# pepitaBadge.net
KiCad netlist of a schematic drawn in EAGLE
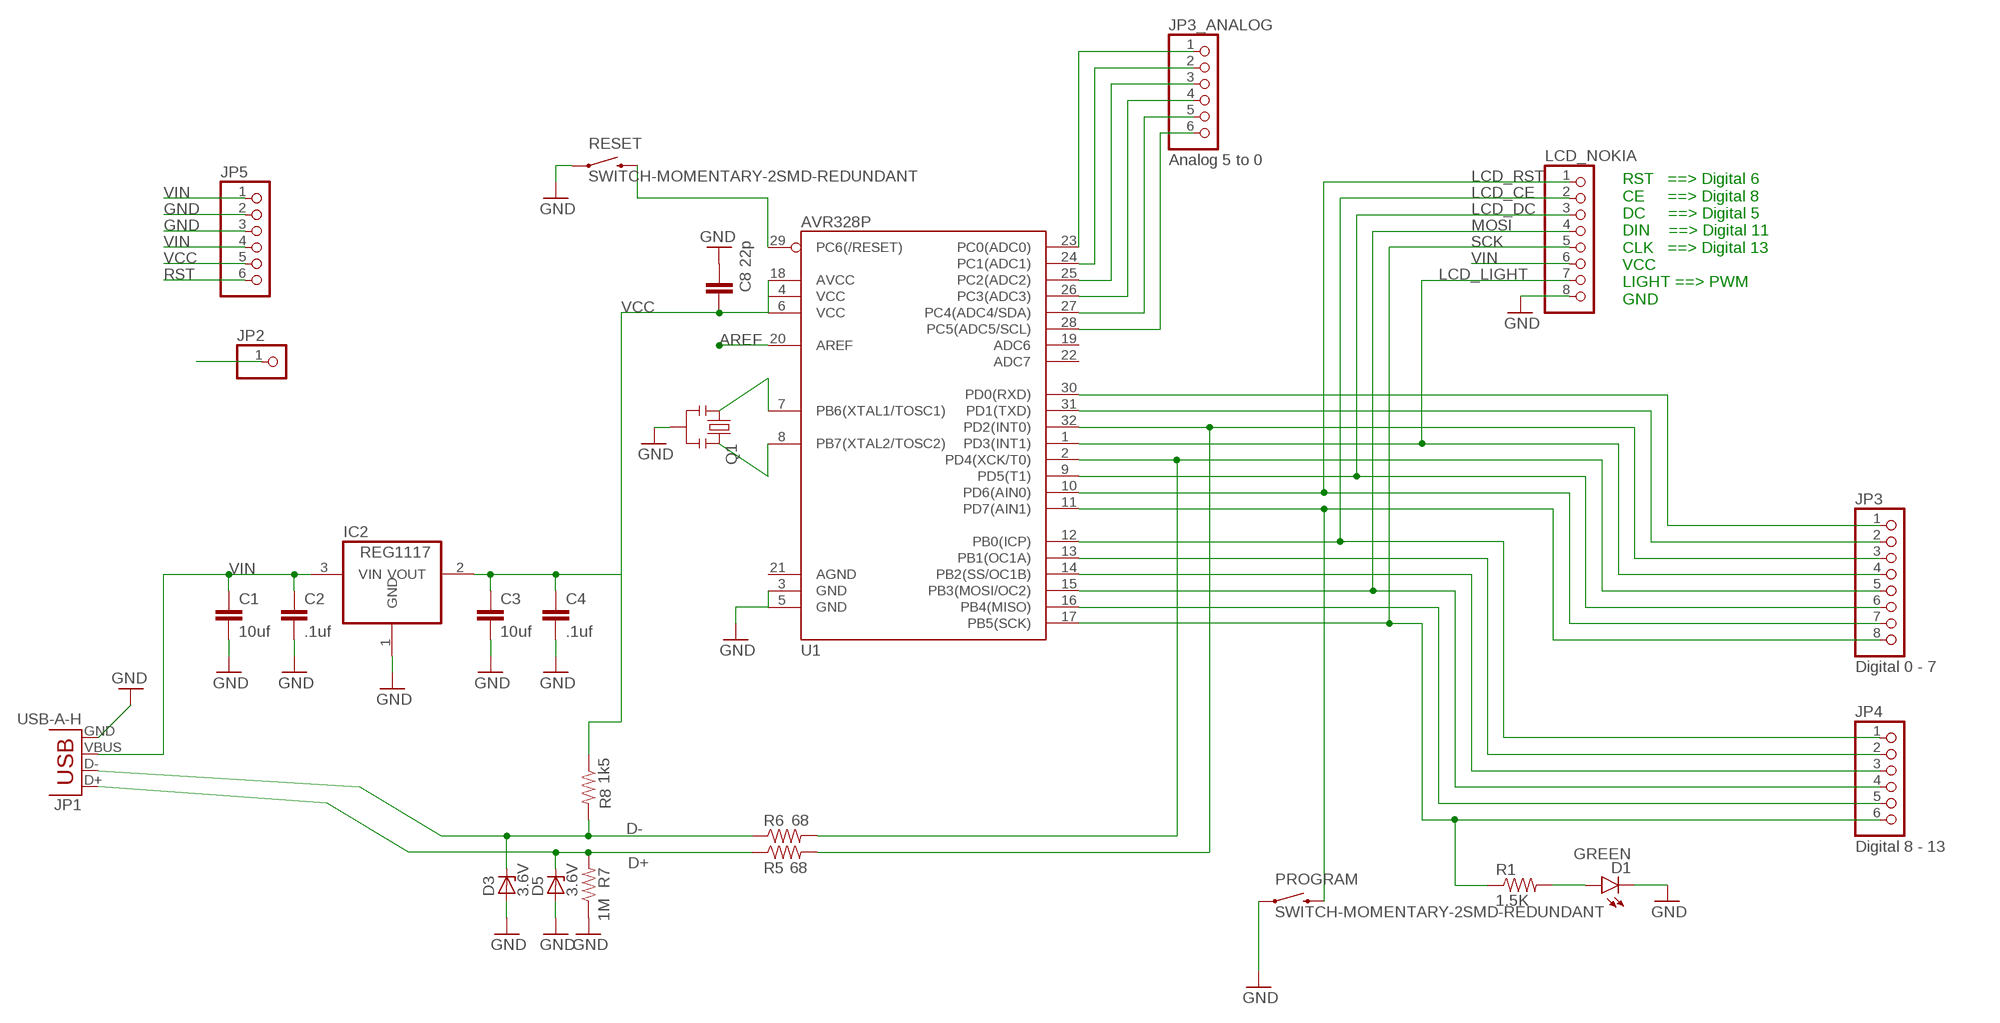
[diagram p0: schematic, sheet 1]

(export (version "E")
  (design (tool "Eeschema 10.0.6"))
  (components
    (comp (ref "C1")
      (value "10uf")
      (footprint "eagle-import:0805")
      (libsource (lib "eagle-import") (part "22UF-6.3V-20%(0805)"))
    )
    (comp (ref "C2")
      (value ".1uf")
      (footprint "eagle-import:0603-CAP")
      (libsource (lib "eagle-import") (part "CAP0603-CAP"))
    )
    (comp (ref "C3")
      (value "10uf")
      (footprint "eagle-import:0805")
      (libsource (lib "eagle-import") (part "22UF-6.3V-20%(0805)"))
    )
    (comp (ref "C4")
      (value ".1uf")
      (footprint "eagle-import:0603-CAP")
      (libsource (lib "eagle-import") (part "CAP0603-CAP"))
    )
    (comp (ref "C8")
      (value "22p")
      (footprint "eagle-import:0603-CAP")
      (libsource (lib "eagle-import") (part "CAP0603-CAP"))
    )
    (comp (ref "D1")
      (value "GREEN")
      (footprint "eagle-import:LED-0603")
      (libsource (lib "eagle-import") (part "LED-GREEN0603"))
    )
    (comp (ref "D3")
      (value "3.6V")
      (footprint "eagle-import:1206")
      (libsource (lib "eagle-import") (part "ZENER-DIODE"))
    )
    (comp (ref "D5")
      (value "3.6V")
      (footprint "eagle-import:1206")
      (libsource (lib "eagle-import") (part "ZENER-DIODE"))
    )
    (comp (ref "IC2")
      (value "REG1117")
      (footprint "eagle-import:SOT223")
      (libsource (lib "eagle-import") (part "REG1117"))
    )
    (comp (ref "JP1")
      (value "USB-A-H")
      (footprint "eagle-import:USB-A-H")
      (libsource (lib "eagle-import") (part "USB-A-H"))
    )
    (comp (ref "JP2")
      (value "PINHD-1X1")
      (footprint "eagle-import:1X01")
      (libsource (lib "eagle-import") (part "PINHD-1X1"))
    )
    (comp (ref "JP3")
      (value "Digital 0 - 7")
      (footprint "eagle-import:1X08")
      (libsource (lib "eagle-import") (part "PINHD-1X8"))
    )
    (comp (ref "JP3_ANALOG")
      (value "Analog 5 to 0")
      (footprint "eagle-import:1X06")
      (libsource (lib "eagle-import") (part "PINHD-1X6"))
    )
    (comp (ref "JP4")
      (value "Digital 8 - 13")
      (footprint "eagle-import:1X06")
      (libsource (lib "eagle-import") (part "PINHD-1X6"))
    )
    (comp (ref "JP5")
      (value "PINHD-1X6")
      (footprint "eagle-import:1X06")
      (libsource (lib "eagle-import") (part "PINHD-1X6"))
    )
    (comp (ref "LCD_NOKIA")
      (value "PINHD-1X8")
      (footprint "eagle-import:1X08")
      (libsource (lib "eagle-import") (part "PINHD-1X8"))
    )
    (comp (ref "PROGRAM")
      (value "SWITCH-MOMENTARY-2SMD-REDUNDANT")
      (footprint "eagle-import:TACTILE-SWITCH-SMD")
      (libsource (lib "eagle-import") (part "SWITCH-MOMENTARY-2SMD-REDUNDANT"))
    )
    (comp (ref "Q1")
      (value "RESONATOR16MHZ")
      (footprint "eagle-import:RESONATOR-SMD")
      (libsource (lib "eagle-import") (part "RESONATOR16MHZ"))
    )
    (comp (ref "R1")
      (value "1.5K")
      (footprint "eagle-import:0603-RES")
      (libsource (lib "eagle-import") (part "RESISTOR0603-RES"))
    )
    (comp (ref "R5")
      (value "68")
      (footprint "eagle-import:0603-RES")
      (libsource (lib "eagle-import") (part "RESISTOR0603-RES"))
    )
    (comp (ref "R6")
      (value "68")
      (footprint "eagle-import:0603-RES")
      (libsource (lib "eagle-import") (part "RESISTOR0603-RES"))
    )
    (comp (ref "R7")
      (value "1M")
      (footprint "eagle-import:0603-RES")
      (libsource (lib "eagle-import") (part "RESISTOR0603-RES"))
    )
    (comp (ref "R8")
      (value "1k5")
      (footprint "eagle-import:0603-RES")
      (libsource (lib "eagle-import") (part "RESISTOR0603-RES"))
    )
    (comp (ref "RESET")
      (value "SWITCH-MOMENTARY-2SMD-REDUNDANT")
      (footprint "eagle-import:TACTILE-SWITCH-SMD")
      (libsource (lib "eagle-import") (part "SWITCH-MOMENTARY-2SMD-REDUNDANT"))
    )
    (comp (ref "U1")
      (value "AVR328P")
      (footprint "eagle-import:TQFP32-08")
      (libsource (lib "eagle-import") (part "ATMEGA328_SMT"))
    )
  )
  (nets
    (net (code "1") (name "/AREF") (class "Default")
      (node (ref "JP2") (pin "1") (pinfunction "1_1") (pintype "passive"))
      (node (ref "U1") (pin "20") (pinfunction "AREF_20") (pintype "bidirectional"))
    )
    (net (code "2") (name "/D+") (class "Default")
      (node (ref "D5") (pin "2") (pinfunction "C_2") (pintype "passive"))
      (node (ref "JP1") (pin "D+") (pinfunction "D+_D+") (pintype "bidirectional"))
      (node (ref "R5") (pin "1") (pinfunction "1_1") (pintype "passive"))
      (node (ref "R7") (pin "2") (pinfunction "2_2") (pintype "passive"))
    )
    (net (code "3") (name "/D-") (class "Default")
      (node (ref "D3") (pin "2") (pinfunction "C_2") (pintype "passive"))
      (node (ref "JP1") (pin "D-") (pinfunction "D-_D-") (pintype "bidirectional"))
      (node (ref "R6") (pin "1") (pinfunction "1_1") (pintype "passive"))
      (node (ref "R8") (pin "2") (pinfunction "2_2") (pintype "passive"))
    )
    (net (code "4") (name "/LCD_CE") (class "Default")
      (node (ref "JP4") (pin "1") (pinfunction "1_1") (pintype "passive"))
      (node (ref "LCD_NOKIA") (pin "2") (pinfunction "2_2") (pintype "passive"))
      (node (ref "U1") (pin "12") (pinfunction "PB0(ICP)_12") (pintype "bidirectional"))
    )
    (net (code "5") (name "/LCD_DC") (class "Default")
      (node (ref "JP3") (pin "6") (pinfunction "6_6") (pintype "passive"))
      (node (ref "LCD_NOKIA") (pin "3") (pinfunction "3_3") (pintype "passive"))
      (node (ref "U1") (pin "9") (pinfunction "PD5(T1)_9") (pintype "bidirectional"))
    )
    (net (code "6") (name "/LCD_LIGHT") (class "Default")
      (node (ref "JP3") (pin "4") (pinfunction "4_4") (pintype "passive"))
      (node (ref "LCD_NOKIA") (pin "7") (pinfunction "7_7") (pintype "passive"))
      (node (ref "U1") (pin "1") (pinfunction "PD3(INT1)_1") (pintype "bidirectional"))
    )
    (net (code "7") (name "/LCD_RST") (class "Default")
      (node (ref "JP3") (pin "7") (pinfunction "7_7") (pintype "passive"))
      (node (ref "LCD_NOKIA") (pin "1") (pinfunction "1_1") (pintype "passive"))
      (node (ref "U1") (pin "10") (pinfunction "PD6(AIN0)_10") (pintype "bidirectional"))
    )
    (net (code "8") (name "/MOSI") (class "Default")
      (node (ref "JP4") (pin "4") (pinfunction "4_4") (pintype "passive"))
      (node (ref "LCD_NOKIA") (pin "4") (pinfunction "4_4") (pintype "passive"))
      (node (ref "U1") (pin "15") (pinfunction "PB3(MOSI/OC2)_15") (pintype "bidirectional"))
    )
    (net (code "9") (name "/RST") (class "Default")
      (node (ref "JP5") (pin "6") (pinfunction "6_6") (pintype "passive"))
      (node (ref "RESET") (pin "3") (pinfunction "2_3") (pintype "passive"))
      (node (ref "RESET") (pin "4") (pinfunction "2_4") (pintype "passive"))
      (node (ref "U1") (pin "29") (pinfunction "PC6(/RESET)_29") (pintype "bidirectional"))
    )
    (net (code "10") (name "/SCK") (class "Default")
      (node (ref "JP4") (pin "6") (pinfunction "6_6") (pintype "passive"))
      (node (ref "LCD_NOKIA") (pin "5") (pinfunction "5_5") (pintype "passive"))
      (node (ref "R1") (pin "1") (pinfunction "1_1") (pintype "passive"))
      (node (ref "U1") (pin "17") (pinfunction "PB5(SCK)_17") (pintype "bidirectional"))
    )
    (net (code "11") (name "/VCC") (class "Default")
      (node (ref "C3") (pin "1") (pinfunction "1_1") (pintype "passive"))
      (node (ref "C4") (pin "1") (pinfunction "1_1") (pintype "passive"))
      (node (ref "C8") (pin "1") (pinfunction "1_1") (pintype "passive"))
      (node (ref "IC2") (pin "2") (pinfunction "VOUT_2") (pintype "output"))
      (node (ref "JP5") (pin "5") (pinfunction "5_5") (pintype "passive"))
      (node (ref "R8") (pin "1") (pinfunction "1_1") (pintype "passive"))
      (node (ref "U1") (pin "18") (pinfunction "AVCC_18") (pintype "bidirectional"))
      (node (ref "U1") (pin "4") (pinfunction "VCC_4") (pintype "bidirectional"))
      (node (ref "U1") (pin "6") (pinfunction "VCC_6") (pintype "bidirectional"))
    )
    (net (code "12") (name "/VIN") (class "Default")
      (node (ref "C1") (pin "1") (pinfunction "1_1") (pintype "passive"))
      (node (ref "C2") (pin "1") (pinfunction "1_1") (pintype "passive"))
      (node (ref "IC2") (pin "3") (pinfunction "VIN_3") (pintype "input"))
      (node (ref "JP1") (pin "VBUS") (pinfunction "VBUS_VBUS") (pintype "bidirectional"))
      (node (ref "JP5") (pin "1") (pinfunction "1_1") (pintype "passive"))
      (node (ref "JP5") (pin "4") (pinfunction "4_4") (pintype "passive"))
      (node (ref "LCD_NOKIA") (pin "6") (pinfunction "6_6") (pintype "passive"))
    )
    (net (code "13") (name "GND") (class "Default")
      (node (ref "C1") (pin "2") (pinfunction "2_2") (pintype "passive"))
      (node (ref "C2") (pin "2") (pinfunction "2_2") (pintype "passive"))
      (node (ref "C3") (pin "2") (pinfunction "2_2") (pintype "passive"))
      (node (ref "C4") (pin "2") (pinfunction "2_2") (pintype "passive"))
      (node (ref "C8") (pin "2") (pinfunction "2_2") (pintype "passive"))
      (node (ref "D1") (pin "C") (pinfunction "C_C") (pintype "passive"))
      (node (ref "D3") (pin "1") (pinfunction "A_1") (pintype "passive"))
      (node (ref "D5") (pin "1") (pinfunction "A_1") (pintype "passive"))
      (node (ref "IC2") (pin "1") (pinfunction "GND_1") (pintype "power_in"))
      (node (ref "JP1") (pin "GND") (pinfunction "GND_GND") (pintype "bidirectional"))
      (node (ref "JP5") (pin "2") (pinfunction "2_2") (pintype "passive"))
      (node (ref "JP5") (pin "3") (pinfunction "3_3") (pintype "passive"))
      (node (ref "LCD_NOKIA") (pin "8") (pinfunction "8_8") (pintype "passive"))
      (node (ref "PROGRAM") (pin "1") (pinfunction "1_1") (pintype "passive"))
      (node (ref "PROGRAM") (pin "2") (pinfunction "1_2") (pintype "passive"))
      (node (ref "Q1") (pin "2") (pinfunction "2_2") (pintype "passive"))
      (node (ref "R7") (pin "1") (pinfunction "1_1") (pintype "passive"))
      (node (ref "RESET") (pin "1") (pinfunction "1_1") (pintype "passive"))
      (node (ref "RESET") (pin "2") (pinfunction "1_2") (pintype "passive"))
      (node (ref "U1") (pin "3") (pinfunction "GND_3") (pintype "bidirectional"))
      (node (ref "U1") (pin "5") (pinfunction "GND_5") (pintype "bidirectional"))
    )
    (net (code "14") (name "Net-(D1-PadA)") (class "Default")
      (node (ref "D1") (pin "A") (pinfunction "A_A") (pintype "passive"))
      (node (ref "R1") (pin "2") (pinfunction "2_2") (pintype "passive"))
    )
    (net (code "15") (name "Net-(U1-PB1(OC1A))") (class "Default")
      (node (ref "JP4") (pin "2") (pinfunction "2_2") (pintype "passive"))
      (node (ref "U1") (pin "13") (pinfunction "PB1(OC1A)_13") (pintype "bidirectional"))
    )
    (net (code "16") (name "Net-(U1-PB2(SS{slash}OC1B))") (class "Default")
      (node (ref "JP4") (pin "3") (pinfunction "3_3") (pintype "passive"))
      (node (ref "U1") (pin "14") (pinfunction "PB2(SS/OC1B)_14") (pintype "bidirectional"))
    )
    (net (code "17") (name "Net-(U1-PB4(MISO))") (class "Default")
      (node (ref "JP4") (pin "5") (pinfunction "5_5") (pintype "passive"))
      (node (ref "U1") (pin "16") (pinfunction "PB4(MISO)_16") (pintype "bidirectional"))
    )
    (net (code "18") (name "Net-(U1-PB6(XTAL1{slash}TOSC1))") (class "Default")
      (node (ref "Q1") (pin "1") (pinfunction "1_1") (pintype "passive"))
      (node (ref "U1") (pin "7") (pinfunction "PB6(XTAL1/TOSC1)_7") (pintype "bidirectional"))
    )
    (net (code "19") (name "Net-(U1-PB7(XTAL2{slash}TOSC2))") (class "Default")
      (node (ref "Q1") (pin "3") (pinfunction "3_3") (pintype "passive"))
      (node (ref "U1") (pin "8") (pinfunction "PB7(XTAL2/TOSC2)_8") (pintype "bidirectional"))
    )
    (net (code "20") (name "Net-(U1-PC0(ADC0))") (class "Default")
      (node (ref "JP3_ANALOG") (pin "1") (pinfunction "1_1") (pintype "passive"))
      (node (ref "U1") (pin "23") (pinfunction "PC0(ADC0)_23") (pintype "bidirectional"))
    )
    (net (code "21") (name "Net-(U1-PC1(ADC1))") (class "Default")
      (node (ref "JP3_ANALOG") (pin "2") (pinfunction "2_2") (pintype "passive"))
      (node (ref "U1") (pin "24") (pinfunction "PC1(ADC1)_24") (pintype "bidirectional"))
    )
    (net (code "22") (name "Net-(U1-PC2(ADC2))") (class "Default")
      (node (ref "JP3_ANALOG") (pin "3") (pinfunction "3_3") (pintype "passive"))
      (node (ref "U1") (pin "25") (pinfunction "PC2(ADC2)_25") (pintype "bidirectional"))
    )
    (net (code "23") (name "Net-(U1-PC3(ADC3))") (class "Default")
      (node (ref "JP3_ANALOG") (pin "4") (pinfunction "4_4") (pintype "passive"))
      (node (ref "U1") (pin "26") (pinfunction "PC3(ADC3)_26") (pintype "bidirectional"))
    )
    (net (code "24") (name "Net-(U1-PC4(ADC4{slash}SDA))") (class "Default")
      (node (ref "JP3_ANALOG") (pin "5") (pinfunction "5_5") (pintype "passive"))
      (node (ref "U1") (pin "27") (pinfunction "PC4(ADC4/SDA)_27") (pintype "bidirectional"))
    )
    (net (code "25") (name "Net-(U1-PC5(ADC5{slash}SCL))") (class "Default")
      (node (ref "JP3_ANALOG") (pin "6") (pinfunction "6_6") (pintype "passive"))
      (node (ref "U1") (pin "28") (pinfunction "PC5(ADC5/SCL)_28") (pintype "bidirectional"))
    )
    (net (code "26") (name "Net-(U1-PD0(RXD))") (class "Default")
      (node (ref "JP3") (pin "1") (pinfunction "1_1") (pintype "passive"))
      (node (ref "U1") (pin "30") (pinfunction "PD0(RXD)_30") (pintype "bidirectional"))
    )
    (net (code "27") (name "Net-(U1-PD1(TXD))") (class "Default")
      (node (ref "JP3") (pin "2") (pinfunction "2_2") (pintype "passive"))
      (node (ref "U1") (pin "31") (pinfunction "PD1(TXD)_31") (pintype "bidirectional"))
    )
    (net (code "28") (name "Net-(U1-PD2(INT0))") (class "Default")
      (node (ref "JP3") (pin "3") (pinfunction "3_3") (pintype "passive"))
      (node (ref "R5") (pin "2") (pinfunction "2_2") (pintype "passive"))
      (node (ref "U1") (pin "32") (pinfunction "PD2(INT0)_32") (pintype "bidirectional"))
    )
    (net (code "29") (name "Net-(U1-PD4(XCK{slash}T0))") (class "Default")
      (node (ref "JP3") (pin "5") (pinfunction "5_5") (pintype "passive"))
      (node (ref "R6") (pin "2") (pinfunction "2_2") (pintype "passive"))
      (node (ref "U1") (pin "2") (pinfunction "PD4(XCK/T0)_2") (pintype "bidirectional"))
    )
    (net (code "30") (name "Net-(U1-PD7(AIN1))") (class "Default")
      (node (ref "JP3") (pin "8") (pinfunction "8_8") (pintype "passive"))
      (node (ref "PROGRAM") (pin "3") (pinfunction "2_3") (pintype "passive"))
      (node (ref "PROGRAM") (pin "4") (pinfunction "2_4") (pintype "passive"))
      (node (ref "U1") (pin "11") (pinfunction "PD7(AIN1)_11") (pintype "bidirectional"))
    )
    (net (code "31") (name "unconnected-(U1-ADC6-Pad19)") (class "Default")
      (node (ref "U1") (pin "19") (pinfunction "ADC6_19") (pintype "bidirectional"))
    )
    (net (code "32") (name "unconnected-(U1-ADC7-Pad22)") (class "Default")
      (node (ref "U1") (pin "22") (pinfunction "ADC7_22") (pintype "bidirectional"))
    )
    (net (code "33") (name "unconnected-(U1-AGND-Pad21)") (class "Default")
      (node (ref "U1") (pin "21") (pinfunction "AGND_21") (pintype "bidirectional"))
    )
  )
)
